# GPSDO_Heater.net
KiCad netlist of a schematic drawn in Altium Designer
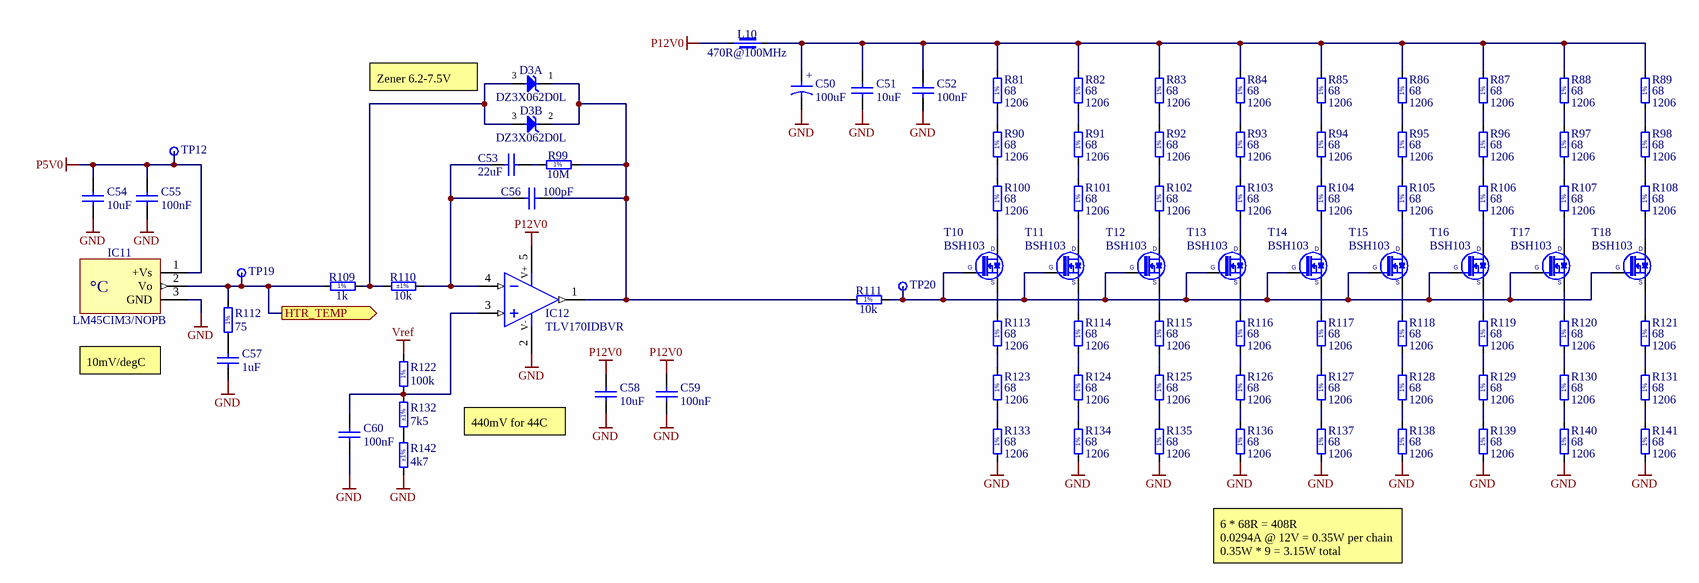
[diagram p0: GPSDO_Heater.SchDoc]

(export (version "E")
  (design (tool "Eeschema 10.0.6"))
  (components
    (comp (ref "C50")
      (value "100uF")
      (footprint "CAPMP7343X310N")
      (description "Polarised capacitor")
      (fields
        (field (name "PART NUMBER") "CTE7343-31_100UF_20V_10%")
        (field (name "VOLTAGE") "20V")
        (field (name "AUTHOR") "CERN DEM JLC")
      )
      (libsource (lib "Capacitors") (part "Capacitor - polarized"))
    )
    (comp (ref "C51")
      (value "10uF")
      (footprint "CAPC1608X80N")
      (description "Non-polarised capacitor")
      (fields
        (field (name "PART NUMBER") "CC0603_10UF_10V_10%_X5R")
        (field (name "VOLTAGE") "10V")
        (field (name "AUTHOR") "CERN DEM JLC")
      )
      (libsource (lib "Capacitors") (part "Capacitor - non polarized"))
    )
    (comp (ref "C52")
      (value "100nF")
      (footprint "CAPC1005X55N")
      (description "Non-polarised capacitor")
      (fields
        (field (name "PART NUMBER") "CC0402_100NF_16V_10%_X5R")
        (field (name "VOLTAGE") "16V")
        (field (name "AUTHOR") "CERN DEM JLC")
      )
      (libsource (lib "Capacitors") (part "Capacitor - non polarized"))
    )
    (comp (ref "C53")
      (value "22uF")
      (footprint "CAPC2012X135N")
      (description "Non-polarised capacitor")
      (fields
        (field (name "MANUFACTURER PART NUMBER") "CC0805_22UF_16V_10%_X5R")
        (field (name "MANUFACTURER") "GENERIC")
        (field (name "AUTHOR") "CERN DEM JLC")
      )
      (libsource (lib "Capacitors") (part "Capacitor - non polarized"))
    )
    (comp (ref "C54")
      (value "10uF")
      (footprint "CAPC1608X80N")
      (description "Non-polarised capacitor")
      (fields
        (field (name "PART NUMBER") "CC0603_10UF_10V_10%_X5R")
        (field (name "VOLTAGE") "10V")
        (field (name "AUTHOR") "CERN DEM JLC")
      )
      (libsource (lib "Capacitors") (part "Capacitor - non polarized"))
    )
    (comp (ref "C55")
      (value "100nF")
      (footprint "CAPC1005X55N")
      (description "Non-polarised capacitor")
      (fields
        (field (name "PART NUMBER") "CC0402_100NF_16V_10%_X5R")
        (field (name "VOLTAGE") "16V")
        (field (name "AUTHOR") "CERN DEM JLC")
      )
      (libsource (lib "Capacitors") (part "Capacitor - non polarized"))
    )
    (comp (ref "C56")
      (value "100pF")
      (footprint "CAPC1005X55N")
      (description "Non-polarised capacitor")
      (fields
        (field (name "PART NUMBER") "CC0402_100PF_50V_5%_C0G")
        (field (name "VOLTAGE") "50V")
        (field (name "AUTHOR") "CERN DEM JLC")
      )
      (libsource (lib "Capacitors") (part "Capacitor - non polarized"))
    )
    (comp (ref "C57")
      (value "1uF")
      (footprint "CAPC1005X55N")
      (description "Non-polarised capacitor")
      (fields
        (field (name "PART NUMBER") "CC0402_1UF_16V_10%_X5R")
        (field (name "VOLTAGE") "16V")
        (field (name "AUTHOR") "CERN DEM JLC")
      )
      (libsource (lib "Capacitors") (part "Capacitor - non polarized"))
    )
    (comp (ref "C58")
      (value "10uF")
      (footprint "CAPC1608X80N")
      (description "Non-polarised capacitor")
      (fields
        (field (name "PART NUMBER") "CC0603_10UF_10V_10%_X5R")
        (field (name "VOLTAGE") "10V")
        (field (name "AUTHOR") "CERN DEM JLC")
      )
      (libsource (lib "Capacitors") (part "Capacitor - non polarized"))
    )
    (comp (ref "C59")
      (value "100nF")
      (footprint "CAPC1005X55N")
      (description "Non-polarised capacitor")
      (fields
        (field (name "PART NUMBER") "CC0402_100NF_16V_10%_X5R")
        (field (name "VOLTAGE") "16V")
        (field (name "AUTHOR") "CERN DEM JLC")
      )
      (libsource (lib "Capacitors") (part "Capacitor - non polarized"))
    )
    (comp (ref "C60")
      (value "100nF")
      (footprint "CAPC1005X55N")
      (description "Non-polarised capacitor")
      (fields
        (field (name "PART NUMBER") "CC0402_100NF_16V_10%_X5R")
        (field (name "VOLTAGE") "16V")
        (field (name "AUTHOR") "CERN DEM JLC")
      )
      (libsource (lib "Capacitors") (part "Capacitor - non polarized"))
    )
    (comp (ref "D3")
      (value "DZ3X062D0L")
      (footprint "SOT95P275X140-3N")
      (description "Dual Common Anode Zener Diode")
      (fields
        (field (name "VOLTAGE") "6.2V")
        (field (name "POWER") "200mA")
        (field (name "AUTHOR") "CERN DEM JLC")
      )
      (libsource (lib "ICs And Semiconductors") (part "Diode Zener x2 C1A3_C2A3"))
    )
    (comp (ref "IC11")
      (value "LM45CIM3/NOPB")
      (footprint "SOT95P251X112-3N")
      (description "-20° to +100°C ±3°C Precision Centigrade Temperature Sensors")
      (fields (field (name "MANUFACTURER") "TEXAS INSTRUMENTS") (field (name "AUTHOR") "CERN DEM JLC"))
      (libsource (lib "ICs And Semiconductors") (part "LM45"))
    )
    (comp (ref "IC12")
      (value "TLV170IDBVR")
      (footprint "SOT95P280X145-5N")
      (description "Low-Power, 36-V Operational Amplifier")
      (fields (field (name "MANUFACTURER") "TEXAS INSTRUMENTS"))
      (libsource (lib "GPSDO") (part "TLV170IDBVR"))
    )
    (comp (ref "L10")
      (value "470R@100MHz")
      (footprint "INDC1608X95N")
      (fields
        (field (name "PART NUMBER") "IND0603_MURATA_BLM18PG471SN1D")
        (field (name "POWER") "1A")
        (field (name "TOLERANCE") "±25%")
        (field (name "AUTHOR") "CERN DEM BC")
      )
      (libsource (lib "Inductors & Transformers") (part "Ferrite Bead"))
    )
    (comp (ref "R81")
      (value "68")
      (footprint "RESC3216X65N")
      (description "Resistor - 1%")
      (fields
        (field (name "PART NUMBER") "R1206_68R_1%_0.25W_100PPM")
        (field (name "POWER") "0.25W")
        (field (name "CASE") "1206")
        (field (name "AUTHOR") "CERN DEM JLC")
      )
      (libsource (lib "Resistors") (part "Resistor - 1%"))
    )
    (comp (ref "R82")
      (value "68")
      (footprint "RESC3216X65N")
      (description "Resistor - 1%")
      (fields
        (field (name "PART NUMBER") "R1206_68R_1%_0.25W_100PPM")
        (field (name "POWER") "0.25W")
        (field (name "CASE") "1206")
        (field (name "AUTHOR") "CERN DEM JLC")
      )
      (libsource (lib "Resistors") (part "Resistor - 1%"))
    )
    (comp (ref "R83")
      (value "68")
      (footprint "RESC3216X65N")
      (description "Resistor - 1%")
      (fields
        (field (name "PART NUMBER") "R1206_68R_1%_0.25W_100PPM")
        (field (name "POWER") "0.25W")
        (field (name "CASE") "1206")
        (field (name "AUTHOR") "CERN DEM JLC")
      )
      (libsource (lib "Resistors") (part "Resistor - 1%"))
    )
    (comp (ref "R84")
      (value "68")
      (footprint "RESC3216X65N")
      (description "Resistor - 1%")
      (fields
        (field (name "PART NUMBER") "R1206_68R_1%_0.25W_100PPM")
        (field (name "POWER") "0.25W")
        (field (name "CASE") "1206")
        (field (name "AUTHOR") "CERN DEM JLC")
      )
      (libsource (lib "Resistors") (part "Resistor - 1%"))
    )
    (comp (ref "R85")
      (value "68")
      (footprint "RESC3216X65N")
      (description "Resistor - 1%")
      (fields
        (field (name "PART NUMBER") "R1206_68R_1%_0.25W_100PPM")
        (field (name "POWER") "0.25W")
        (field (name "CASE") "1206")
        (field (name "AUTHOR") "CERN DEM JLC")
      )
      (libsource (lib "Resistors") (part "Resistor - 1%"))
    )
    (comp (ref "R86")
      (value "68")
      (footprint "RESC3216X65N")
      (description "Resistor - 1%")
      (fields
        (field (name "PART NUMBER") "R1206_68R_1%_0.25W_100PPM")
        (field (name "POWER") "0.25W")
        (field (name "CASE") "1206")
        (field (name "AUTHOR") "CERN DEM JLC")
      )
      (libsource (lib "Resistors") (part "Resistor - 1%"))
    )
    (comp (ref "R87")
      (value "68")
      (footprint "RESC3216X65N")
      (description "Resistor - 1%")
      (fields
        (field (name "PART NUMBER") "R1206_68R_1%_0.25W_100PPM")
        (field (name "POWER") "0.25W")
        (field (name "CASE") "1206")
        (field (name "AUTHOR") "CERN DEM JLC")
      )
      (libsource (lib "Resistors") (part "Resistor - 1%"))
    )
    (comp (ref "R88")
      (value "68")
      (footprint "RESC3216X65N")
      (description "Resistor - 1%")
      (fields
        (field (name "PART NUMBER") "R1206_68R_1%_0.25W_100PPM")
        (field (name "POWER") "0.25W")
        (field (name "CASE") "1206")
        (field (name "AUTHOR") "CERN DEM JLC")
      )
      (libsource (lib "Resistors") (part "Resistor - 1%"))
    )
    (comp (ref "R89")
      (value "68")
      (footprint "RESC3216X65N")
      (description "Resistor - 1%")
      (fields
        (field (name "PART NUMBER") "R1206_68R_1%_0.25W_100PPM")
        (field (name "POWER") "0.25W")
        (field (name "CASE") "1206")
        (field (name "AUTHOR") "CERN DEM JLC")
      )
      (libsource (lib "Resistors") (part "Resistor - 1%"))
    )
    (comp (ref "R90")
      (value "68")
      (footprint "RESC3216X65N")
      (description "Resistor - 1%")
      (fields
        (field (name "PART NUMBER") "R1206_68R_1%_0.25W_100PPM")
        (field (name "POWER") "0.25W")
        (field (name "CASE") "1206")
        (field (name "AUTHOR") "CERN DEM JLC")
      )
      (libsource (lib "Resistors") (part "Resistor - 1%"))
    )
    (comp (ref "R91")
      (value "68")
      (footprint "RESC3216X65N")
      (description "Resistor - 1%")
      (fields
        (field (name "PART NUMBER") "R1206_68R_1%_0.25W_100PPM")
        (field (name "POWER") "0.25W")
        (field (name "CASE") "1206")
        (field (name "AUTHOR") "CERN DEM JLC")
      )
      (libsource (lib "Resistors") (part "Resistor - 1%"))
    )
    (comp (ref "R92")
      (value "68")
      (footprint "RESC3216X65N")
      (description "Resistor - 1%")
      (fields
        (field (name "PART NUMBER") "R1206_68R_1%_0.25W_100PPM")
        (field (name "POWER") "0.25W")
        (field (name "CASE") "1206")
        (field (name "AUTHOR") "CERN DEM JLC")
      )
      (libsource (lib "Resistors") (part "Resistor - 1%"))
    )
    (comp (ref "R93")
      (value "68")
      (footprint "RESC3216X65N")
      (description "Resistor - 1%")
      (fields
        (field (name "PART NUMBER") "R1206_68R_1%_0.25W_100PPM")
        (field (name "POWER") "0.25W")
        (field (name "CASE") "1206")
        (field (name "AUTHOR") "CERN DEM JLC")
      )
      (libsource (lib "Resistors") (part "Resistor - 1%"))
    )
    (comp (ref "R94")
      (value "68")
      (footprint "RESC3216X65N")
      (description "Resistor - 1%")
      (fields
        (field (name "PART NUMBER") "R1206_68R_1%_0.25W_100PPM")
        (field (name "POWER") "0.25W")
        (field (name "CASE") "1206")
        (field (name "AUTHOR") "CERN DEM JLC")
      )
      (libsource (lib "Resistors") (part "Resistor - 1%"))
    )
    (comp (ref "R95")
      (value "68")
      (footprint "RESC3216X65N")
      (description "Resistor - 1%")
      (fields
        (field (name "PART NUMBER") "R1206_68R_1%_0.25W_100PPM")
        (field (name "POWER") "0.25W")
        (field (name "CASE") "1206")
        (field (name "AUTHOR") "CERN DEM JLC")
      )
      (libsource (lib "Resistors") (part "Resistor - 1%"))
    )
    (comp (ref "R96")
      (value "68")
      (footprint "RESC3216X65N")
      (description "Resistor - 1%")
      (fields
        (field (name "PART NUMBER") "R1206_68R_1%_0.25W_100PPM")
        (field (name "POWER") "0.25W")
        (field (name "CASE") "1206")
        (field (name "AUTHOR") "CERN DEM JLC")
      )
      (libsource (lib "Resistors") (part "Resistor - 1%"))
    )
    (comp (ref "R97")
      (value "68")
      (footprint "RESC3216X65N")
      (description "Resistor - 1%")
      (fields
        (field (name "PART NUMBER") "R1206_68R_1%_0.25W_100PPM")
        (field (name "POWER") "0.25W")
        (field (name "CASE") "1206")
        (field (name "AUTHOR") "CERN DEM JLC")
      )
      (libsource (lib "Resistors") (part "Resistor - 1%"))
    )
    (comp (ref "R98")
      (value "68")
      (footprint "RESC3216X65N")
      (description "Resistor - 1%")
      (fields
        (field (name "PART NUMBER") "R1206_68R_1%_0.25W_100PPM")
        (field (name "POWER") "0.25W")
        (field (name "CASE") "1206")
        (field (name "AUTHOR") "CERN DEM JLC")
      )
      (libsource (lib "Resistors") (part "Resistor - 1%"))
    )
    (comp (ref "R99")
      (value "10M")
      (footprint "RESC2113X55N")
      (description "Resistor - 1%")
      (fields
        (field (name "PART NUMBER") "R0805_10M_1%_0.125W_100PPM_VISHAY_CRCW e3")
        (field (name "POWER") "0.125W")
        (field (name "AUTHOR") "CERN DEM BC")
      )
      (libsource (lib "Resistors") (part "Resistor - 1%"))
    )
    (comp (ref "R100")
      (value "68")
      (footprint "RESC3216X65N")
      (description "Resistor - 1%")
      (fields
        (field (name "PART NUMBER") "R1206_68R_1%_0.25W_100PPM")
        (field (name "POWER") "0.25W")
        (field (name "CASE") "1206")
        (field (name "AUTHOR") "CERN DEM JLC")
      )
      (libsource (lib "Resistors") (part "Resistor - 1%"))
    )
    (comp (ref "R101")
      (value "68")
      (footprint "RESC3216X65N")
      (description "Resistor - 1%")
      (fields
        (field (name "PART NUMBER") "R1206_68R_1%_0.25W_100PPM")
        (field (name "POWER") "0.25W")
        (field (name "CASE") "1206")
        (field (name "AUTHOR") "CERN DEM JLC")
      )
      (libsource (lib "Resistors") (part "Resistor - 1%"))
    )
    (comp (ref "R102")
      (value "68")
      (footprint "RESC3216X65N")
      (description "Resistor - 1%")
      (fields
        (field (name "PART NUMBER") "R1206_68R_1%_0.25W_100PPM")
        (field (name "POWER") "0.25W")
        (field (name "CASE") "1206")
        (field (name "AUTHOR") "CERN DEM JLC")
      )
      (libsource (lib "Resistors") (part "Resistor - 1%"))
    )
    (comp (ref "R103")
      (value "68")
      (footprint "RESC3216X65N")
      (description "Resistor - 1%")
      (fields
        (field (name "PART NUMBER") "R1206_68R_1%_0.25W_100PPM")
        (field (name "POWER") "0.25W")
        (field (name "CASE") "1206")
        (field (name "AUTHOR") "CERN DEM JLC")
      )
      (libsource (lib "Resistors") (part "Resistor - 1%"))
    )
    (comp (ref "R104")
      (value "68")
      (footprint "RESC3216X65N")
      (description "Resistor - 1%")
      (fields
        (field (name "PART NUMBER") "R1206_68R_1%_0.25W_100PPM")
        (field (name "POWER") "0.25W")
        (field (name "CASE") "1206")
        (field (name "AUTHOR") "CERN DEM JLC")
      )
      (libsource (lib "Resistors") (part "Resistor - 1%"))
    )
    (comp (ref "R105")
      (value "68")
      (footprint "RESC3216X65N")
      (description "Resistor - 1%")
      (fields
        (field (name "PART NUMBER") "R1206_68R_1%_0.25W_100PPM")
        (field (name "POWER") "0.25W")
        (field (name "CASE") "1206")
        (field (name "AUTHOR") "CERN DEM JLC")
      )
      (libsource (lib "Resistors") (part "Resistor - 1%"))
    )
    (comp (ref "R106")
      (value "68")
      (footprint "RESC3216X65N")
      (description "Resistor - 1%")
      (fields
        (field (name "PART NUMBER") "R1206_68R_1%_0.25W_100PPM")
        (field (name "POWER") "0.25W")
        (field (name "CASE") "1206")
        (field (name "AUTHOR") "CERN DEM JLC")
      )
      (libsource (lib "Resistors") (part "Resistor - 1%"))
    )
    (comp (ref "R107")
      (value "68")
      (footprint "RESC3216X65N")
      (description "Resistor - 1%")
      (fields
        (field (name "PART NUMBER") "R1206_68R_1%_0.25W_100PPM")
        (field (name "POWER") "0.25W")
        (field (name "CASE") "1206")
        (field (name "AUTHOR") "CERN DEM JLC")
      )
      (libsource (lib "Resistors") (part "Resistor - 1%"))
    )
    (comp (ref "R108")
      (value "68")
      (footprint "RESC3216X65N")
      (description "Resistor - 1%")
      (fields
        (field (name "PART NUMBER") "R1206_68R_1%_0.25W_100PPM")
        (field (name "POWER") "0.25W")
        (field (name "CASE") "1206")
        (field (name "AUTHOR") "CERN DEM JLC")
      )
      (libsource (lib "Resistors") (part "Resistor - 1%"))
    )
    (comp (ref "R109")
      (value "1k")
      (footprint "RESC1005X40N")
      (description "Resistor - 1%")
      (fields
        (field (name "PART NUMBER") "R0402_1K_1%_0.0625W_100PPM")
        (field (name "POWER") "0.0625W")
        (field (name "AUTHOR") "CERN DEM JLC")
      )
      (libsource (lib "Resistors") (part "Resistor - 1%"))
    )
    (comp (ref "R110")
      (value "10k")
      (footprint "RESC1005X40N")
      (description "Resistor - 1%")
      (fields
        (field (name "TOLERANCE") "±1%")
        (field (name "PART NUMBER") "R0402_10K_1%_0.0625W_100PPM")
        (field (name "POWER") "0.0625W")
        (field (name "AUTHOR") "CERN DEM JLC")
      )
      (libsource (lib "") (part "Resistor - 1%_1"))
    )
    (comp (ref "R111")
      (value "10k")
      (footprint "RESC1005X40N")
      (description "Resistor - 1%")
      (fields
        (field (name "PART NUMBER") "R0402_10K_1%_0.0625W_100PPM")
        (field (name "POWER") "0.0625W")
        (field (name "AUTHOR") "CERN DEM JLC")
      )
      (libsource (lib "Resistors") (part "Resistor - 1%"))
    )
    (comp (ref "R112")
      (value "75")
      (footprint "RESC1005X40N")
      (description "Resistor - 1%")
      (fields
        (field (name "PART NUMBER") "R0402_75R_1%_0.0625W_100PPM")
        (field (name "POWER") "0.0625W")
        (field (name "AUTHOR") "CERN DEM JLC")
      )
      (libsource (lib "Resistors") (part "Resistor - 1%"))
    )
    (comp (ref "R113")
      (value "68")
      (footprint "RESC3216X65N")
      (description "Resistor - 1%")
      (fields
        (field (name "PART NUMBER") "R1206_68R_1%_0.25W_100PPM")
        (field (name "POWER") "0.25W")
        (field (name "CASE") "1206")
        (field (name "AUTHOR") "CERN DEM JLC")
      )
      (libsource (lib "Resistors") (part "Resistor - 1%"))
    )
    (comp (ref "R114")
      (value "68")
      (footprint "RESC3216X65N")
      (description "Resistor - 1%")
      (fields
        (field (name "PART NUMBER") "R1206_68R_1%_0.25W_100PPM")
        (field (name "POWER") "0.25W")
        (field (name "CASE") "1206")
        (field (name "AUTHOR") "CERN DEM JLC")
      )
      (libsource (lib "Resistors") (part "Resistor - 1%"))
    )
    (comp (ref "R115")
      (value "68")
      (footprint "RESC3216X65N")
      (description "Resistor - 1%")
      (fields
        (field (name "PART NUMBER") "R1206_68R_1%_0.25W_100PPM")
        (field (name "POWER") "0.25W")
        (field (name "CASE") "1206")
        (field (name "AUTHOR") "CERN DEM JLC")
      )
      (libsource (lib "Resistors") (part "Resistor - 1%"))
    )
    (comp (ref "R116")
      (value "68")
      (footprint "RESC3216X65N")
      (description "Resistor - 1%")
      (fields
        (field (name "PART NUMBER") "R1206_68R_1%_0.25W_100PPM")
        (field (name "POWER") "0.25W")
        (field (name "CASE") "1206")
        (field (name "AUTHOR") "CERN DEM JLC")
      )
      (libsource (lib "Resistors") (part "Resistor - 1%"))
    )
    (comp (ref "R117")
      (value "68")
      (footprint "RESC3216X65N")
      (description "Resistor - 1%")
      (fields
        (field (name "PART NUMBER") "R1206_68R_1%_0.25W_100PPM")
        (field (name "POWER") "0.25W")
        (field (name "CASE") "1206")
        (field (name "AUTHOR") "CERN DEM JLC")
      )
      (libsource (lib "Resistors") (part "Resistor - 1%"))
    )
    (comp (ref "R118")
      (value "68")
      (footprint "RESC3216X65N")
      (description "Resistor - 1%")
      (fields
        (field (name "PART NUMBER") "R1206_68R_1%_0.25W_100PPM")
        (field (name "POWER") "0.25W")
        (field (name "CASE") "1206")
        (field (name "AUTHOR") "CERN DEM JLC")
      )
      (libsource (lib "Resistors") (part "Resistor - 1%"))
    )
    (comp (ref "R119")
      (value "68")
      (footprint "RESC3216X65N")
      (description "Resistor - 1%")
      (fields
        (field (name "PART NUMBER") "R1206_68R_1%_0.25W_100PPM")
        (field (name "POWER") "0.25W")
        (field (name "CASE") "1206")
        (field (name "AUTHOR") "CERN DEM JLC")
      )
      (libsource (lib "Resistors") (part "Resistor - 1%"))
    )
    (comp (ref "R120")
      (value "68")
      (footprint "RESC3216X65N")
      (description "Resistor - 1%")
      (fields
        (field (name "PART NUMBER") "R1206_68R_1%_0.25W_100PPM")
        (field (name "POWER") "0.25W")
        (field (name "CASE") "1206")
        (field (name "AUTHOR") "CERN DEM JLC")
      )
      (libsource (lib "Resistors") (part "Resistor - 1%"))
    )
    (comp (ref "R121")
      (value "68")
      (footprint "RESC3216X65N")
      (description "Resistor - 1%")
      (fields
        (field (name "PART NUMBER") "R1206_68R_1%_0.25W_100PPM")
        (field (name "POWER") "0.25W")
        (field (name "CASE") "1206")
        (field (name "AUTHOR") "CERN DEM JLC")
      )
      (libsource (lib "Resistors") (part "Resistor - 1%"))
    )
    (comp (ref "R122")
      (value "100k")
      (footprint "RESC1005X40N")
      (description "Resistor - 1%")
      (fields
        (field (name "PART NUMBER") "R0402_100K_1%_0.0625W_100PPM")
        (field (name "POWER") "0.0625W")
        (field (name "AUTHOR") "CERN DEM JLC")
      )
      (libsource (lib "Resistors") (part "Resistor - 1%"))
    )
    (comp (ref "R123")
      (value "68")
      (footprint "RESC3216X65N")
      (description "Resistor - 1%")
      (fields
        (field (name "PART NUMBER") "R1206_68R_1%_0.25W_100PPM")
        (field (name "POWER") "0.25W")
        (field (name "CASE") "1206")
        (field (name "AUTHOR") "CERN DEM JLC")
      )
      (libsource (lib "Resistors") (part "Resistor - 1%"))
    )
    (comp (ref "R124")
      (value "68")
      (footprint "RESC3216X65N")
      (description "Resistor - 1%")
      (fields
        (field (name "PART NUMBER") "R1206_68R_1%_0.25W_100PPM")
        (field (name "POWER") "0.25W")
        (field (name "CASE") "1206")
        (field (name "AUTHOR") "CERN DEM JLC")
      )
      (libsource (lib "Resistors") (part "Resistor - 1%"))
    )
    (comp (ref "R125")
      (value "68")
      (footprint "RESC3216X65N")
      (description "Resistor - 1%")
      (fields
        (field (name "PART NUMBER") "R1206_68R_1%_0.25W_100PPM")
        (field (name "POWER") "0.25W")
        (field (name "CASE") "1206")
        (field (name "AUTHOR") "CERN DEM JLC")
      )
      (libsource (lib "Resistors") (part "Resistor - 1%"))
    )
    (comp (ref "R126")
      (value "68")
      (footprint "RESC3216X65N")
      (description "Resistor - 1%")
      (fields
        (field (name "PART NUMBER") "R1206_68R_1%_0.25W_100PPM")
        (field (name "POWER") "0.25W")
        (field (name "CASE") "1206")
        (field (name "AUTHOR") "CERN DEM JLC")
      )
      (libsource (lib "Resistors") (part "Resistor - 1%"))
    )
    (comp (ref "R127")
      (value "68")
      (footprint "RESC3216X65N")
      (description "Resistor - 1%")
      (fields
        (field (name "PART NUMBER") "R1206_68R_1%_0.25W_100PPM")
        (field (name "POWER") "0.25W")
        (field (name "CASE") "1206")
        (field (name "AUTHOR") "CERN DEM JLC")
      )
      (libsource (lib "Resistors") (part "Resistor - 1%"))
    )
    (comp (ref "R128")
      (value "68")
      (footprint "RESC3216X65N")
      (description "Resistor - 1%")
      (fields
        (field (name "PART NUMBER") "R1206_68R_1%_0.25W_100PPM")
        (field (name "POWER") "0.25W")
        (field (name "CASE") "1206")
        (field (name "AUTHOR") "CERN DEM JLC")
      )
      (libsource (lib "Resistors") (part "Resistor - 1%"))
    )
    (comp (ref "R129")
      (value "68")
      (footprint "RESC3216X65N")
      (description "Resistor - 1%")
      (fields
        (field (name "PART NUMBER") "R1206_68R_1%_0.25W_100PPM")
        (field (name "POWER") "0.25W")
        (field (name "CASE") "1206")
        (field (name "AUTHOR") "CERN DEM JLC")
      )
      (libsource (lib "Resistors") (part "Resistor - 1%"))
    )
    (comp (ref "R130")
      (value "68")
      (footprint "RESC3216X65N")
      (description "Resistor - 1%")
      (fields
        (field (name "PART NUMBER") "R1206_68R_1%_0.25W_100PPM")
        (field (name "POWER") "0.25W")
        (field (name "CASE") "1206")
        (field (name "AUTHOR") "CERN DEM JLC")
      )
      (libsource (lib "Resistors") (part "Resistor - 1%"))
    )
    (comp (ref "R131")
      (value "68")
      (footprint "RESC3216X65N")
      (description "Resistor - 1%")
      (fields
        (field (name "PART NUMBER") "R1206_68R_1%_0.25W_100PPM")
        (field (name "POWER") "0.25W")
        (field (name "CASE") "1206")
        (field (name "AUTHOR") "CERN DEM JLC")
      )
      (libsource (lib "Resistors") (part "Resistor - 1%"))
    )
    (comp (ref "R132")
      (value "7k5")
      (footprint "RESC1005X40N")
      (description "Resistor - 1%")
      (fields
        (field (name "TOLERANCE") "±1%")
        (field (name "PART NUMBER") "R0402_7K5_1%_0.0625W_100PPM")
        (field (name "POWER") "0.0625W")
        (field (name "AUTHOR") "CERN DEM JLC")
      )
      (libsource (lib "") (part "Resistor - 1%_1"))
    )
    (comp (ref "R133")
      (value "68")
      (footprint "RESC3216X65N")
      (description "Resistor - 1%")
      (fields
        (field (name "PART NUMBER") "R1206_68R_1%_0.25W_100PPM")
        (field (name "POWER") "0.25W")
        (field (name "CASE") "1206")
        (field (name "AUTHOR") "CERN DEM JLC")
      )
      (libsource (lib "Resistors") (part "Resistor - 1%"))
    )
    (comp (ref "R134")
      (value "68")
      (footprint "RESC3216X65N")
      (description "Resistor - 1%")
      (fields
        (field (name "PART NUMBER") "R1206_68R_1%_0.25W_100PPM")
        (field (name "POWER") "0.25W")
        (field (name "CASE") "1206")
        (field (name "AUTHOR") "CERN DEM JLC")
      )
      (libsource (lib "Resistors") (part "Resistor - 1%"))
    )
    (comp (ref "R135")
      (value "68")
      (footprint "RESC3216X65N")
      (description "Resistor - 1%")
      (fields
        (field (name "PART NUMBER") "R1206_68R_1%_0.25W_100PPM")
        (field (name "POWER") "0.25W")
        (field (name "CASE") "1206")
        (field (name "AUTHOR") "CERN DEM JLC")
      )
      (libsource (lib "Resistors") (part "Resistor - 1%"))
    )
    (comp (ref "R136")
      (value "68")
      (footprint "RESC3216X65N")
      (description "Resistor - 1%")
      (fields
        (field (name "PART NUMBER") "R1206_68R_1%_0.25W_100PPM")
        (field (name "POWER") "0.25W")
        (field (name "CASE") "1206")
        (field (name "AUTHOR") "CERN DEM JLC")
      )
      (libsource (lib "Resistors") (part "Resistor - 1%"))
    )
    (comp (ref "R137")
      (value "68")
      (footprint "RESC3216X65N")
      (description "Resistor - 1%")
      (fields
        (field (name "PART NUMBER") "R1206_68R_1%_0.25W_100PPM")
        (field (name "POWER") "0.25W")
        (field (name "CASE") "1206")
        (field (name "AUTHOR") "CERN DEM JLC")
      )
      (libsource (lib "Resistors") (part "Resistor - 1%"))
    )
    (comp (ref "R138")
      (value "68")
      (footprint "RESC3216X65N")
      (description "Resistor - 1%")
      (fields
        (field (name "PART NUMBER") "R1206_68R_1%_0.25W_100PPM")
        (field (name "POWER") "0.25W")
        (field (name "CASE") "1206")
        (field (name "AUTHOR") "CERN DEM JLC")
      )
      (libsource (lib "Resistors") (part "Resistor - 1%"))
    )
    (comp (ref "R139")
      (value "68")
      (footprint "RESC3216X65N")
      (description "Resistor - 1%")
      (fields
        (field (name "PART NUMBER") "R1206_68R_1%_0.25W_100PPM")
        (field (name "POWER") "0.25W")
        (field (name "CASE") "1206")
        (field (name "AUTHOR") "CERN DEM JLC")
      )
      (libsource (lib "Resistors") (part "Resistor - 1%"))
    )
    (comp (ref "R140")
      (value "68")
      (footprint "RESC3216X65N")
      (description "Resistor - 1%")
      (fields
        (field (name "PART NUMBER") "R1206_68R_1%_0.25W_100PPM")
        (field (name "POWER") "0.25W")
        (field (name "CASE") "1206")
        (field (name "AUTHOR") "CERN DEM JLC")
      )
      (libsource (lib "Resistors") (part "Resistor - 1%"))
    )
    (comp (ref "R141")
      (value "68")
      (footprint "RESC3216X65N")
      (description "Resistor - 1%")
      (fields
        (field (name "PART NUMBER") "R1206_68R_1%_0.25W_100PPM")
        (field (name "POWER") "0.25W")
        (field (name "CASE") "1206")
        (field (name "AUTHOR") "CERN DEM JLC")
      )
      (libsource (lib "Resistors") (part "Resistor - 1%"))
    )
    (comp (ref "R142")
      (value "4k7")
      (footprint "RESC1005X40N")
      (description "Resistor - 1%")
      (fields
        (field (name "TOLERANCE") "±1%")
        (field (name "PART NUMBER") "R0402_4K7_1%_0.0625W_100PPM")
        (field (name "POWER") "0.0625W")
        (field (name "AUTHOR") "CERN DEM JLC")
      )
      (libsource (lib "") (part "Resistor - 1%_1"))
    )
    (comp (ref "T10")
      (value "BSH103")
      (footprint "SOT95P230X110-3N")
      (description "N-CHANNEL MOSFET WITH DIODE")
      (fields (field (name "MANUFACTURER") "NEXPERIA") (field (name "AUTHOR") "CERN DEM JLC"))
      (libsource (lib "ICs And Semiconductors") (part "N-MOSFET-D 1G 2S 3D"))
    )
    (comp (ref "T11")
      (value "BSH103")
      (footprint "SOT95P230X110-3N")
      (description "N-CHANNEL MOSFET WITH DIODE")
      (fields (field (name "MANUFACTURER") "NEXPERIA") (field (name "AUTHOR") "CERN DEM JLC"))
      (libsource (lib "ICs And Semiconductors") (part "N-MOSFET-D 1G 2S 3D"))
    )
    (comp (ref "T12")
      (value "BSH103")
      (footprint "SOT95P230X110-3N")
      (description "N-CHANNEL MOSFET WITH DIODE")
      (fields (field (name "MANUFACTURER") "NEXPERIA") (field (name "AUTHOR") "CERN DEM JLC"))
      (libsource (lib "ICs And Semiconductors") (part "N-MOSFET-D 1G 2S 3D"))
    )
    (comp (ref "T13")
      (value "BSH103")
      (footprint "SOT95P230X110-3N")
      (description "N-CHANNEL MOSFET WITH DIODE")
      (fields (field (name "MANUFACTURER") "NEXPERIA") (field (name "AUTHOR") "CERN DEM JLC"))
      (libsource (lib "ICs And Semiconductors") (part "N-MOSFET-D 1G 2S 3D"))
    )
    (comp (ref "T14")
      (value "BSH103")
      (footprint "SOT95P230X110-3N")
      (description "N-CHANNEL MOSFET WITH DIODE")
      (fields (field (name "MANUFACTURER") "NEXPERIA") (field (name "AUTHOR") "CERN DEM JLC"))
      (libsource (lib "ICs And Semiconductors") (part "N-MOSFET-D 1G 2S 3D"))
    )
    (comp (ref "T15")
      (value "BSH103")
      (footprint "SOT95P230X110-3N")
      (description "N-CHANNEL MOSFET WITH DIODE")
      (fields (field (name "MANUFACTURER") "NEXPERIA") (field (name "AUTHOR") "CERN DEM JLC"))
      (libsource (lib "ICs And Semiconductors") (part "N-MOSFET-D 1G 2S 3D"))
    )
    (comp (ref "T16")
      (value "BSH103")
      (footprint "SOT95P230X110-3N")
      (description "N-CHANNEL MOSFET WITH DIODE")
      (fields (field (name "MANUFACTURER") "NEXPERIA") (field (name "AUTHOR") "CERN DEM JLC"))
      (libsource (lib "ICs And Semiconductors") (part "N-MOSFET-D 1G 2S 3D"))
    )
    (comp (ref "T17")
      (value "BSH103")
      (footprint "SOT95P230X110-3N")
      (description "N-CHANNEL MOSFET WITH DIODE")
      (fields (field (name "MANUFACTURER") "NEXPERIA") (field (name "AUTHOR") "CERN DEM JLC"))
      (libsource (lib "ICs And Semiconductors") (part "N-MOSFET-D 1G 2S 3D"))
    )
    (comp (ref "T18")
      (value "BSH103")
      (footprint "SOT95P230X110-3N")
      (description "N-CHANNEL MOSFET WITH DIODE")
      (fields (field (name "MANUFACTURER") "NEXPERIA") (field (name "AUTHOR") "CERN DEM JLC"))
      (libsource (lib "ICs And Semiconductors") (part "N-MOSFET-D 1G 2S 3D"))
    )
    (comp (ref "TP12")
      (value "Test Point")
      (footprint "TPS127")
      (fields (field (name "PART NUMBER") "SMD_PAD_1.27X1.27MM") (field (name "AUTHOR") "CERN DEM JLC"))
      (libsource (lib "Eletro-mechanical") (part "Test Point"))
    )
    (comp (ref "TP19")
      (value "Test Point")
      (footprint "TPS127")
      (fields (field (name "PART NUMBER") "SMD_PAD_1.27X1.27MM") (field (name "AUTHOR") "CERN DEM JLC"))
      (libsource (lib "Eletro-mechanical") (part "Test Point"))
    )
    (comp (ref "TP20")
      (value "Test Point")
      (footprint "TPS127")
      (fields (field (name "PART NUMBER") "SMD_PAD_1.27X1.27MM") (field (name "AUTHOR") "CERN DEM JLC"))
      (libsource (lib "Eletro-mechanical") (part "Test Point"))
    )
  )
  (nets
    (net (code "1") (name "/HTR_TEMP") (class "Default")
      (node (ref "IC11") (pin "2") (pinfunction "Vo_2") (pintype "output"))
      (node (ref "R109") (pin "1") (pinfunction "1_1") (pintype "passive"))
      (node (ref "R112") (pin "2") (pinfunction "2_2") (pintype "passive"))
      (node (ref "TP19") (pin "1") (pinfunction "1_1") (pintype "bidirectional"))
    )
    (net (code "2") (name "GND") (class "Default")
      (node (ref "C50") (pin "2") (pinfunction "2_2") (pintype "passive"))
      (node (ref "C51") (pin "1") (pinfunction "1_1") (pintype "passive"))
      (node (ref "C52") (pin "1") (pinfunction "1_1") (pintype "passive"))
      (node (ref "C54") (pin "1") (pinfunction "1_1") (pintype "passive"))
      (node (ref "C55") (pin "1") (pinfunction "1_1") (pintype "passive"))
      (node (ref "C57") (pin "1") (pinfunction "1_1") (pintype "passive"))
      (node (ref "C58") (pin "1") (pinfunction "1_1") (pintype "passive"))
      (node (ref "C59") (pin "1") (pinfunction "1_1") (pintype "passive"))
      (node (ref "C60") (pin "1") (pinfunction "1_1") (pintype "passive"))
      (node (ref "IC11") (pin "3") (pinfunction "GND_3") (pintype "power_in"))
      (node (ref "IC12") (pin "2") (pinfunction "V-_2") (pintype "power_in"))
      (node (ref "R133") (pin "1") (pinfunction "1_1") (pintype "passive"))
      (node (ref "R134") (pin "1") (pinfunction "1_1") (pintype "passive"))
      (node (ref "R135") (pin "1") (pinfunction "1_1") (pintype "passive"))
      (node (ref "R136") (pin "1") (pinfunction "1_1") (pintype "passive"))
      (node (ref "R137") (pin "1") (pinfunction "1_1") (pintype "passive"))
      (node (ref "R138") (pin "1") (pinfunction "1_1") (pintype "passive"))
      (node (ref "R139") (pin "1") (pinfunction "1_1") (pintype "passive"))
      (node (ref "R140") (pin "1") (pinfunction "1_1") (pintype "passive"))
      (node (ref "R141") (pin "1") (pinfunction "1_1") (pintype "passive"))
      (node (ref "R142") (pin "1") (pinfunction "1_1") (pintype "passive"))
    )
    (net (code "3") (name "Net-(C50-Pad1)") (class "Default")
      (node (ref "C50") (pin "1") (pinfunction "1_1") (pintype "passive"))
      (node (ref "C51") (pin "2") (pinfunction "2_2") (pintype "passive"))
      (node (ref "C52") (pin "2") (pinfunction "2_2") (pintype "passive"))
      (node (ref "L10") (pin "2") (pinfunction "2_2") (pintype "passive"))
      (node (ref "R81") (pin "2") (pinfunction "2_2") (pintype "passive"))
      (node (ref "R82") (pin "2") (pinfunction "2_2") (pintype "passive"))
      (node (ref "R83") (pin "2") (pinfunction "2_2") (pintype "passive"))
      (node (ref "R84") (pin "2") (pinfunction "2_2") (pintype "passive"))
      (node (ref "R85") (pin "2") (pinfunction "2_2") (pintype "passive"))
      (node (ref "R86") (pin "2") (pinfunction "2_2") (pintype "passive"))
      (node (ref "R87") (pin "2") (pinfunction "2_2") (pintype "passive"))
      (node (ref "R88") (pin "2") (pinfunction "2_2") (pintype "passive"))
      (node (ref "R89") (pin "2") (pinfunction "2_2") (pintype "passive"))
    )
    (net (code "4") (name "Net-(C53-Pad2)") (class "Default")
      (node (ref "C53") (pin "2") (pinfunction "2_2") (pintype "passive"))
      (node (ref "R99") (pin "1") (pinfunction "1_1") (pintype "passive"))
    )
    (net (code "5") (name "Net-(C57-Pad2)") (class "Default")
      (node (ref "C57") (pin "2") (pinfunction "2_2") (pintype "passive"))
      (node (ref "R112") (pin "1") (pinfunction "1_1") (pintype "passive"))
    )
    (net (code "6") (name "Net-(D3A-C)") (class "Default")
      (node (ref "C56") (pin "2") (pinfunction "2_2") (pintype "passive"))
      (node (ref "D3") (pin "1") (pinfunction "C_1") (pintype "passive"))
      (node (ref "D3") (pin "2") (pinfunction "C_2") (pintype "passive"))
      (node (ref "IC12") (pin "1") (pinfunction "OUT_1") (pintype "output"))
      (node (ref "R111") (pin "1") (pinfunction "1_1") (pintype "passive"))
      (node (ref "R99") (pin "2") (pinfunction "2_2") (pintype "passive"))
    )
    (net (code "7") (name "Net-(D3A-COMA)") (class "Default")
      (node (ref "D3") (pin "3") (pinfunction "COMA_3") (pintype "passive"))
      (node (ref "R109") (pin "2") (pinfunction "2_2") (pintype "passive"))
      (node (ref "R110") (pin "1") (pinfunction "1_1") (pintype "passive"))
    )
    (net (code "8") (name "Net-(IC12-IN+)") (class "Default")
      (node (ref "C60") (pin "2") (pinfunction "2_2") (pintype "passive"))
      (node (ref "IC12") (pin "3") (pinfunction "IN+_3") (pintype "input"))
      (node (ref "R122") (pin "1") (pinfunction "1_1") (pintype "passive"))
      (node (ref "R132") (pin "2") (pinfunction "2_2") (pintype "passive"))
    )
    (net (code "9") (name "Net-(IC12-IN-)") (class "Default")
      (node (ref "C53") (pin "1") (pinfunction "1_1") (pintype "passive"))
      (node (ref "C56") (pin "1") (pinfunction "1_1") (pintype "passive"))
      (node (ref "IC12") (pin "4") (pinfunction "IN-_4") (pintype "input"))
      (node (ref "R110") (pin "2") (pinfunction "2_2") (pintype "passive"))
    )
    (net (code "10") (name "Net-(R81-Pad1)") (class "Default")
      (node (ref "R81") (pin "1") (pinfunction "1_1") (pintype "passive"))
      (node (ref "R90") (pin "2") (pinfunction "2_2") (pintype "passive"))
    )
    (net (code "11") (name "Net-(R82-Pad1)") (class "Default")
      (node (ref "R82") (pin "1") (pinfunction "1_1") (pintype "passive"))
      (node (ref "R91") (pin "2") (pinfunction "2_2") (pintype "passive"))
    )
    (net (code "12") (name "Net-(R83-Pad1)") (class "Default")
      (node (ref "R83") (pin "1") (pinfunction "1_1") (pintype "passive"))
      (node (ref "R92") (pin "2") (pinfunction "2_2") (pintype "passive"))
    )
    (net (code "13") (name "Net-(R84-Pad1)") (class "Default")
      (node (ref "R84") (pin "1") (pinfunction "1_1") (pintype "passive"))
      (node (ref "R93") (pin "2") (pinfunction "2_2") (pintype "passive"))
    )
    (net (code "14") (name "Net-(R85-Pad1)") (class "Default")
      (node (ref "R85") (pin "1") (pinfunction "1_1") (pintype "passive"))
      (node (ref "R94") (pin "2") (pinfunction "2_2") (pintype "passive"))
    )
    (net (code "15") (name "Net-(R86-Pad1)") (class "Default")
      (node (ref "R86") (pin "1") (pinfunction "1_1") (pintype "passive"))
      (node (ref "R95") (pin "2") (pinfunction "2_2") (pintype "passive"))
    )
    (net (code "16") (name "Net-(R87-Pad1)") (class "Default")
      (node (ref "R87") (pin "1") (pinfunction "1_1") (pintype "passive"))
      (node (ref "R96") (pin "2") (pinfunction "2_2") (pintype "passive"))
    )
    (net (code "17") (name "Net-(R88-Pad1)") (class "Default")
      (node (ref "R88") (pin "1") (pinfunction "1_1") (pintype "passive"))
      (node (ref "R97") (pin "2") (pinfunction "2_2") (pintype "passive"))
    )
    (net (code "18") (name "Net-(R89-Pad1)") (class "Default")
      (node (ref "R89") (pin "1") (pinfunction "1_1") (pintype "passive"))
      (node (ref "R98") (pin "2") (pinfunction "2_2") (pintype "passive"))
    )
    (net (code "19") (name "Net-(R100-Pad2)") (class "Default")
      (node (ref "R100") (pin "2") (pinfunction "2_2") (pintype "passive"))
      (node (ref "R90") (pin "1") (pinfunction "1_1") (pintype "passive"))
    )
    (net (code "20") (name "Net-(R101-Pad2)") (class "Default")
      (node (ref "R101") (pin "2") (pinfunction "2_2") (pintype "passive"))
      (node (ref "R91") (pin "1") (pinfunction "1_1") (pintype "passive"))
    )
    (net (code "21") (name "Net-(R102-Pad2)") (class "Default")
      (node (ref "R102") (pin "2") (pinfunction "2_2") (pintype "passive"))
      (node (ref "R92") (pin "1") (pinfunction "1_1") (pintype "passive"))
    )
    (net (code "22") (name "Net-(R103-Pad2)") (class "Default")
      (node (ref "R103") (pin "2") (pinfunction "2_2") (pintype "passive"))
      (node (ref "R93") (pin "1") (pinfunction "1_1") (pintype "passive"))
    )
    (net (code "23") (name "Net-(R104-Pad2)") (class "Default")
      (node (ref "R104") (pin "2") (pinfunction "2_2") (pintype "passive"))
      (node (ref "R94") (pin "1") (pinfunction "1_1") (pintype "passive"))
    )
    (net (code "24") (name "Net-(R105-Pad2)") (class "Default")
      (node (ref "R105") (pin "2") (pinfunction "2_2") (pintype "passive"))
      (node (ref "R95") (pin "1") (pinfunction "1_1") (pintype "passive"))
    )
    (net (code "25") (name "Net-(R106-Pad2)") (class "Default")
      (node (ref "R106") (pin "2") (pinfunction "2_2") (pintype "passive"))
      (node (ref "R96") (pin "1") (pinfunction "1_1") (pintype "passive"))
    )
    (net (code "26") (name "Net-(R107-Pad2)") (class "Default")
      (node (ref "R107") (pin "2") (pinfunction "2_2") (pintype "passive"))
      (node (ref "R97") (pin "1") (pinfunction "1_1") (pintype "passive"))
    )
    (net (code "27") (name "Net-(R108-Pad2)") (class "Default")
      (node (ref "R108") (pin "2") (pinfunction "2_2") (pintype "passive"))
      (node (ref "R98") (pin "1") (pinfunction "1_1") (pintype "passive"))
    )
    (net (code "28") (name "Net-(R113-Pad1)") (class "Default")
      (node (ref "R113") (pin "1") (pinfunction "1_1") (pintype "passive"))
      (node (ref "R123") (pin "2") (pinfunction "2_2") (pintype "passive"))
    )
    (net (code "29") (name "Net-(R114-Pad1)") (class "Default")
      (node (ref "R114") (pin "1") (pinfunction "1_1") (pintype "passive"))
      (node (ref "R124") (pin "2") (pinfunction "2_2") (pintype "passive"))
    )
    (net (code "30") (name "Net-(R115-Pad1)") (class "Default")
      (node (ref "R115") (pin "1") (pinfunction "1_1") (pintype "passive"))
      (node (ref "R125") (pin "2") (pinfunction "2_2") (pintype "passive"))
    )
    (net (code "31") (name "Net-(R116-Pad1)") (class "Default")
      (node (ref "R116") (pin "1") (pinfunction "1_1") (pintype "passive"))
      (node (ref "R126") (pin "2") (pinfunction "2_2") (pintype "passive"))
    )
    (net (code "32") (name "Net-(R117-Pad1)") (class "Default")
      (node (ref "R117") (pin "1") (pinfunction "1_1") (pintype "passive"))
      (node (ref "R127") (pin "2") (pinfunction "2_2") (pintype "passive"))
    )
    (net (code "33") (name "Net-(R118-Pad1)") (class "Default")
      (node (ref "R118") (pin "1") (pinfunction "1_1") (pintype "passive"))
      (node (ref "R128") (pin "2") (pinfunction "2_2") (pintype "passive"))
    )
    (net (code "34") (name "Net-(R119-Pad1)") (class "Default")
      (node (ref "R119") (pin "1") (pinfunction "1_1") (pintype "passive"))
      (node (ref "R129") (pin "2") (pinfunction "2_2") (pintype "passive"))
    )
    (net (code "35") (name "Net-(R120-Pad1)") (class "Default")
      (node (ref "R120") (pin "1") (pinfunction "1_1") (pintype "passive"))
      (node (ref "R130") (pin "2") (pinfunction "2_2") (pintype "passive"))
    )
    (net (code "36") (name "Net-(R121-Pad1)") (class "Default")
      (node (ref "R121") (pin "1") (pinfunction "1_1") (pintype "passive"))
      (node (ref "R131") (pin "2") (pinfunction "2_2") (pintype "passive"))
    )
    (net (code "37") (name "Net-(R123-Pad1)") (class "Default")
      (node (ref "R123") (pin "1") (pinfunction "1_1") (pintype "passive"))
      (node (ref "R133") (pin "2") (pinfunction "2_2") (pintype "passive"))
    )
    (net (code "38") (name "Net-(R124-Pad1)") (class "Default")
      (node (ref "R124") (pin "1") (pinfunction "1_1") (pintype "passive"))
      (node (ref "R134") (pin "2") (pinfunction "2_2") (pintype "passive"))
    )
    (net (code "39") (name "Net-(R125-Pad1)") (class "Default")
      (node (ref "R125") (pin "1") (pinfunction "1_1") (pintype "passive"))
      (node (ref "R135") (pin "2") (pinfunction "2_2") (pintype "passive"))
    )
    (net (code "40") (name "Net-(R126-Pad1)") (class "Default")
      (node (ref "R126") (pin "1") (pinfunction "1_1") (pintype "passive"))
      (node (ref "R136") (pin "2") (pinfunction "2_2") (pintype "passive"))
    )
    (net (code "41") (name "Net-(R127-Pad1)") (class "Default")
      (node (ref "R127") (pin "1") (pinfunction "1_1") (pintype "passive"))
      (node (ref "R137") (pin "2") (pinfunction "2_2") (pintype "passive"))
    )
    (net (code "42") (name "Net-(R128-Pad1)") (class "Default")
      (node (ref "R128") (pin "1") (pinfunction "1_1") (pintype "passive"))
      (node (ref "R138") (pin "2") (pinfunction "2_2") (pintype "passive"))
    )
    (net (code "43") (name "Net-(R129-Pad1)") (class "Default")
      (node (ref "R129") (pin "1") (pinfunction "1_1") (pintype "passive"))
      (node (ref "R139") (pin "2") (pinfunction "2_2") (pintype "passive"))
    )
    (net (code "44") (name "Net-(R130-Pad1)") (class "Default")
      (node (ref "R130") (pin "1") (pinfunction "1_1") (pintype "passive"))
      (node (ref "R140") (pin "2") (pinfunction "2_2") (pintype "passive"))
    )
    (net (code "45") (name "Net-(R131-Pad1)") (class "Default")
      (node (ref "R131") (pin "1") (pinfunction "1_1") (pintype "passive"))
      (node (ref "R141") (pin "2") (pinfunction "2_2") (pintype "passive"))
    )
    (net (code "46") (name "Net-(R132-Pad1)") (class "Default")
      (node (ref "R132") (pin "1") (pinfunction "1_1") (pintype "passive"))
      (node (ref "R142") (pin "2") (pinfunction "2_2") (pintype "passive"))
    )
    (net (code "47") (name "Net-(T10-D)") (class "Default")
      (node (ref "R100") (pin "1") (pinfunction "1_1") (pintype "passive"))
      (node (ref "T10") (pin "3") (pinfunction "D_3") (pintype "passive"))
    )
    (net (code "48") (name "Net-(T10-G)") (class "Default")
      (node (ref "R111") (pin "2") (pinfunction "2_2") (pintype "passive"))
      (node (ref "T10") (pin "1") (pinfunction "G_1") (pintype "passive"))
      (node (ref "T11") (pin "1") (pinfunction "G_1") (pintype "passive"))
      (node (ref "T12") (pin "1") (pinfunction "G_1") (pintype "passive"))
      (node (ref "T13") (pin "1") (pinfunction "G_1") (pintype "passive"))
      (node (ref "T14") (pin "1") (pinfunction "G_1") (pintype "passive"))
      (node (ref "T15") (pin "1") (pinfunction "G_1") (pintype "passive"))
      (node (ref "T16") (pin "1") (pinfunction "G_1") (pintype "passive"))
      (node (ref "T17") (pin "1") (pinfunction "G_1") (pintype "passive"))
      (node (ref "T18") (pin "1") (pinfunction "G_1") (pintype "passive"))
      (node (ref "TP20") (pin "1") (pinfunction "1_1") (pintype "bidirectional"))
    )
    (net (code "49") (name "Net-(T10-S)") (class "Default")
      (node (ref "R113") (pin "2") (pinfunction "2_2") (pintype "passive"))
      (node (ref "T10") (pin "2") (pinfunction "S_2") (pintype "passive"))
    )
    (net (code "50") (name "Net-(T11-D)") (class "Default")
      (node (ref "R101") (pin "1") (pinfunction "1_1") (pintype "passive"))
      (node (ref "T11") (pin "3") (pinfunction "D_3") (pintype "passive"))
    )
    (net (code "51") (name "Net-(T11-S)") (class "Default")
      (node (ref "R114") (pin "2") (pinfunction "2_2") (pintype "passive"))
      (node (ref "T11") (pin "2") (pinfunction "S_2") (pintype "passive"))
    )
    (net (code "52") (name "Net-(T12-D)") (class "Default")
      (node (ref "R102") (pin "1") (pinfunction "1_1") (pintype "passive"))
      (node (ref "T12") (pin "3") (pinfunction "D_3") (pintype "passive"))
    )
    (net (code "53") (name "Net-(T12-S)") (class "Default")
      (node (ref "R115") (pin "2") (pinfunction "2_2") (pintype "passive"))
      (node (ref "T12") (pin "2") (pinfunction "S_2") (pintype "passive"))
    )
    (net (code "54") (name "Net-(T13-D)") (class "Default")
      (node (ref "R103") (pin "1") (pinfunction "1_1") (pintype "passive"))
      (node (ref "T13") (pin "3") (pinfunction "D_3") (pintype "passive"))
    )
    (net (code "55") (name "Net-(T13-S)") (class "Default")
      (node (ref "R116") (pin "2") (pinfunction "2_2") (pintype "passive"))
      (node (ref "T13") (pin "2") (pinfunction "S_2") (pintype "passive"))
    )
    (net (code "56") (name "Net-(T14-D)") (class "Default")
      (node (ref "R104") (pin "1") (pinfunction "1_1") (pintype "passive"))
      (node (ref "T14") (pin "3") (pinfunction "D_3") (pintype "passive"))
    )
    (net (code "57") (name "Net-(T14-S)") (class "Default")
      (node (ref "R117") (pin "2") (pinfunction "2_2") (pintype "passive"))
      (node (ref "T14") (pin "2") (pinfunction "S_2") (pintype "passive"))
    )
    (net (code "58") (name "Net-(T15-D)") (class "Default")
      (node (ref "R105") (pin "1") (pinfunction "1_1") (pintype "passive"))
      (node (ref "T15") (pin "3") (pinfunction "D_3") (pintype "passive"))
    )
    (net (code "59") (name "Net-(T15-S)") (class "Default")
      (node (ref "R118") (pin "2") (pinfunction "2_2") (pintype "passive"))
      (node (ref "T15") (pin "2") (pinfunction "S_2") (pintype "passive"))
    )
    (net (code "60") (name "Net-(T16-D)") (class "Default")
      (node (ref "R106") (pin "1") (pinfunction "1_1") (pintype "passive"))
      (node (ref "T16") (pin "3") (pinfunction "D_3") (pintype "passive"))
    )
    (net (code "61") (name "Net-(T16-S)") (class "Default")
      (node (ref "R119") (pin "2") (pinfunction "2_2") (pintype "passive"))
      (node (ref "T16") (pin "2") (pinfunction "S_2") (pintype "passive"))
    )
    (net (code "62") (name "Net-(T17-D)") (class "Default")
      (node (ref "R107") (pin "1") (pinfunction "1_1") (pintype "passive"))
      (node (ref "T17") (pin "3") (pinfunction "D_3") (pintype "passive"))
    )
    (net (code "63") (name "Net-(T17-S)") (class "Default")
      (node (ref "R120") (pin "2") (pinfunction "2_2") (pintype "passive"))
      (node (ref "T17") (pin "2") (pinfunction "S_2") (pintype "passive"))
    )
    (net (code "64") (name "Net-(T18-D)") (class "Default")
      (node (ref "R108") (pin "1") (pinfunction "1_1") (pintype "passive"))
      (node (ref "T18") (pin "3") (pinfunction "D_3") (pintype "passive"))
    )
    (net (code "65") (name "Net-(T18-S)") (class "Default")
      (node (ref "R121") (pin "2") (pinfunction "2_2") (pintype "passive"))
      (node (ref "T18") (pin "2") (pinfunction "S_2") (pintype "passive"))
    )
    (net (code "66") (name "P5V0") (class "Default")
      (node (ref "C54") (pin "2") (pinfunction "2_2") (pintype "passive"))
      (node (ref "C55") (pin "2") (pinfunction "2_2") (pintype "passive"))
      (node (ref "IC11") (pin "1") (pinfunction "+Vs_1") (pintype "power_in"))
      (node (ref "TP12") (pin "1") (pinfunction "1_1") (pintype "bidirectional"))
    )
    (net (code "67") (name "P12V0") (class "Default")
      (node (ref "C58") (pin "2") (pinfunction "2_2") (pintype "passive"))
      (node (ref "C59") (pin "2") (pinfunction "2_2") (pintype "passive"))
      (node (ref "IC12") (pin "5") (pinfunction "V+_5") (pintype "power_in"))
      (node (ref "L10") (pin "1") (pinfunction "1_1") (pintype "passive"))
    )
    (net (code "68") (name "Vref") (class "Default")
      (node (ref "R122") (pin "2") (pinfunction "2_2") (pintype "passive"))
    )
  )
)
